# ADCs.net
KiCad netlist of a schematic drawn in Altium Designer
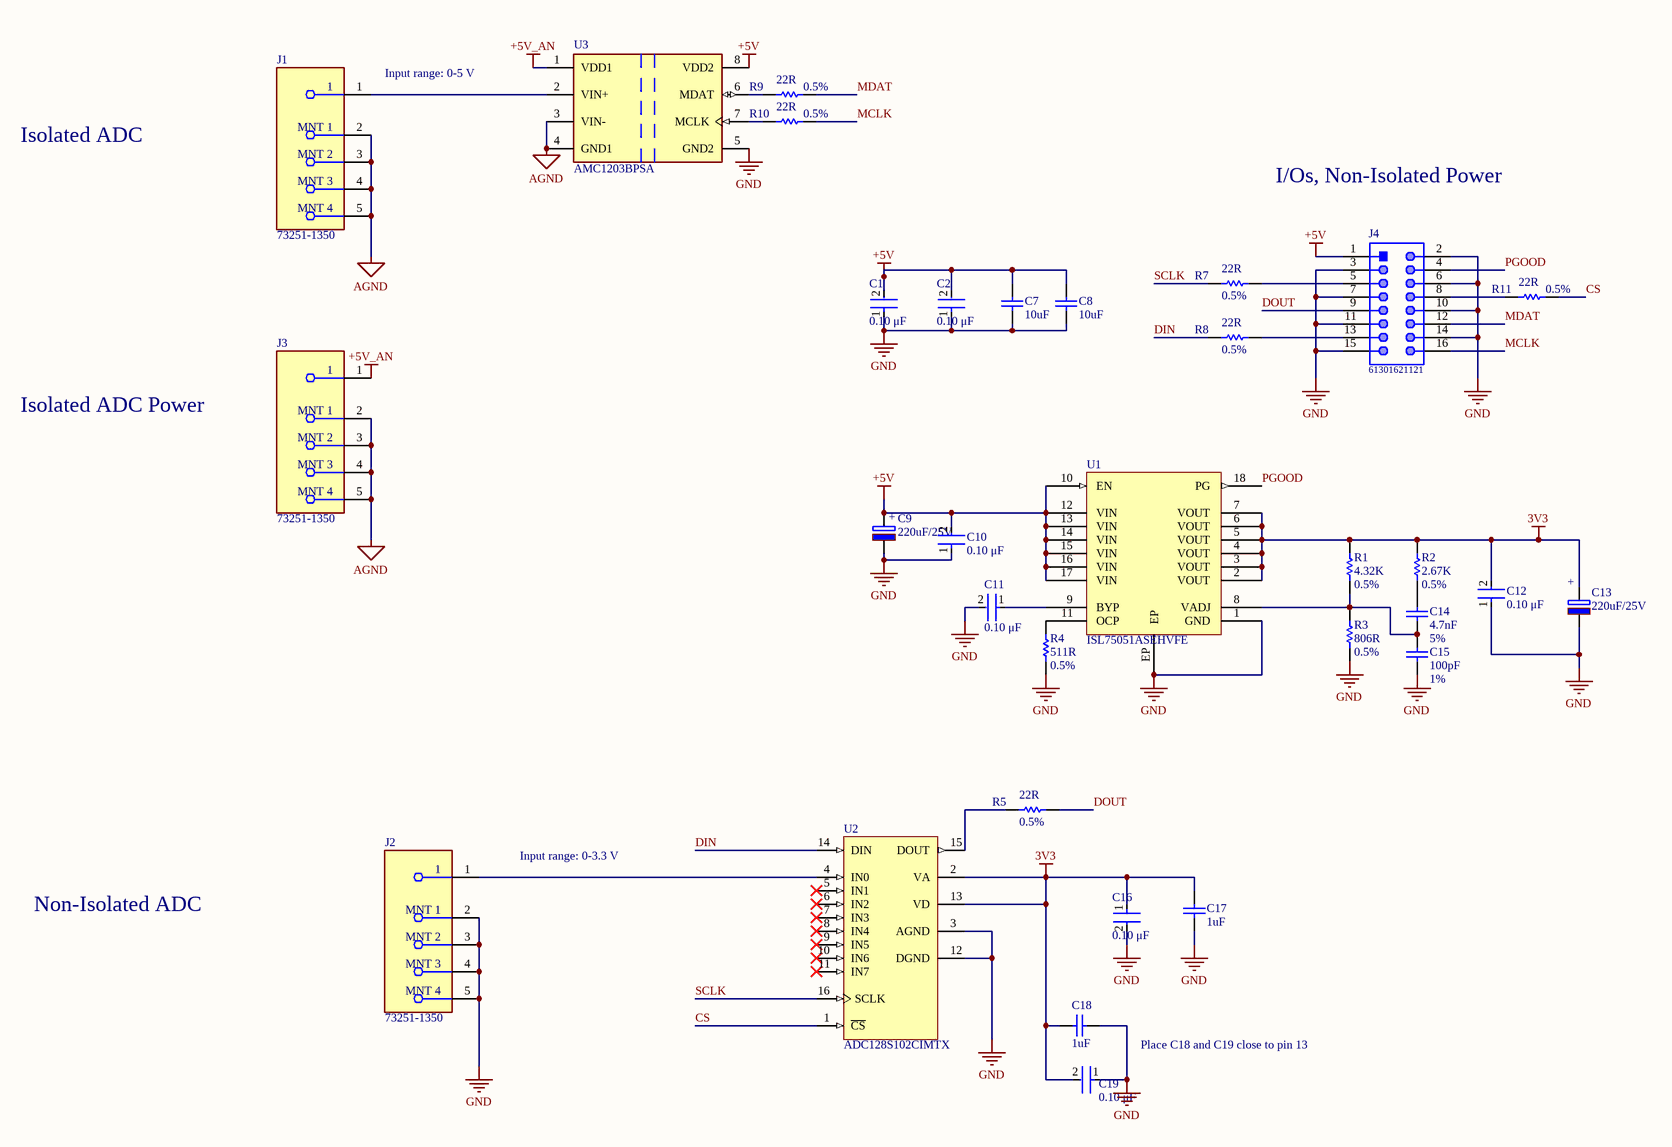
[diagram p0: ADCs.SchDoc]

(export (version "E")
  (design (tool "Eeschema 10.0.6"))
  (components
    (comp (ref "C1")
      (value "0.10 μF")
      (footprint "FP-C0603C-CF-MFG")
      (description "CAP CER 0.1UF 50V 5% X7R 0603")
      (fields (field (name "TOLERANCE") "0.05") (field (name "MANUFACTURER PART NUMBER") "C0603C104J5RACTU"))
      (libsource (lib "Isolated-ADCs") (part "CMP-2006-03056-2"))
    )
    (comp (ref "C2")
      (value "0.10 μF")
      (footprint "FP-C0603C-CF-MFG")
      (description "CAP CER 0.1UF 50V 5% X7R 0603")
      (fields (field (name "TOLERANCE") "0.05") (field (name "MANUFACTURER PART NUMBER") "C0603C104J5RACTU"))
      (libsource (lib "Isolated-ADCs") (part "CMP-2006-03056-2"))
    )
    (comp (ref "C7")
      (value "10uF")
      (footprint "CAPC1608X90N")
      (description "CAP CER 10UF 25V X5R 0603")
      (fields
        (field (name "MANUFACTURER PART NUMBER") "GRM188R61E106KA73D")
        (field (name "MANUFACTURER") "Murata Electronics")
      )
      (libsource (lib "Isolated-ADCs") (part "CAP CER 10UF 25V X5R 0603"))
    )
    (comp (ref "C8")
      (value "10uF")
      (footprint "CAPC1608X90N")
      (description "CAP CER 10UF 25V X5R 0603")
      (fields
        (field (name "MANUFACTURER PART NUMBER") "GRM188R61E106KA73D")
        (field (name "MANUFACTURER") "Murata Electronics")
      )
      (libsource (lib "Isolated-ADCs") (part "CAP CER 10UF 25V X5R 0603"))
    )
    (comp (ref "C9")
      (value "220uF/25V")
      (footprint "CAP_AE830X1050N")
      (description "CAP ALUM 220UF 20% 25V SMD")
      (fields
        (field (name "MANUFACTURER PART NUMBER") "EMZA250ADA221MHA0G")
        (field (name "MANUFACTURER") "United Chemi-Con")
      )
      (libsource (lib "Isolated-ADCs") (part "CAP ALUM 220UF 20% 25V SMD"))
    )
    (comp (ref "C10")
      (value "0.10 μF")
      (footprint "FP-C0603C-CF-MFG")
      (description "CAP CER 0.1UF 50V 5% X7R 0603")
      (fields
        (field (name "MANUFACTURER PART NUMBER") "C0603C104J5RACTU")
        (field (name "MANUFACTURER") "KEMET")
      )
      (libsource (lib "Isolated-ADCs") (part "CMP-2006-03056-2"))
    )
    (comp (ref "C11")
      (value "0.10 μF")
      (footprint "FP-C0603C-CF-MFG")
      (description "CAP CER 0.1UF 50V 5% X7R 0603")
      (fields
        (field (name "MANUFACTURER PART NUMBER") "C0603C104J5RACTU")
        (field (name "MANUFACTURER") "KEMET")
      )
      (libsource (lib "Isolated-ADCs") (part "CMP-2006-03056-2"))
    )
    (comp (ref "C12")
      (value "0.10 μF")
      (footprint "FP-C0603C-CF-MFG")
      (description "CAP CER 0.1UF 50V 5% X7R 0603")
      (fields
        (field (name "MANUFACTURER PART NUMBER") "C0603C104J5RACTU")
        (field (name "MANUFACTURER") "KEMET")
      )
      (libsource (lib "Isolated-ADCs") (part "CMP-2006-03056-2"))
    )
    (comp (ref "C13")
      (value "220uF/25V")
      (footprint "CAP_AE830X1050N")
      (description "CAP ALUM 220UF 20% 25V SMD")
      (fields
        (field (name "MANUFACTURER PART NUMBER") "EMZA250ADA221MHA0G")
        (field (name "MANUFACTURER") "United Chemi-Con")
      )
      (libsource (lib "") (part "CAP ALUM 220UF 20% 25V SMD_1"))
    )
    (comp (ref "C14")
      (value "4.7nF")
      (footprint "CAPC1608X90N")
      (description "CAP CER 4700PF 50V C0G 0603")
      (fields
        (field (name "MANUFACTURER PART NUMBER") "CGA3E2C0G1H472J080AA")
        (field (name "MANUFACTURER") "TDK Corporation")
        (field (name "TOLERANCE") "5%")
      )
      (libsource (lib "Isolated-ADCs") (part "CAP CER 4700PF 50V C0G 0603"))
    )
    (comp (ref "C15")
      (value "100pF")
      (footprint "CAPC1608X90N")
      (description "CAP CER 100PF 50V C0G/NP0 0603")
      (fields
        (field (name "MANUFACTURER PART NUMBER") "06035A101FAT2A")
        (field (name "MANUFACTURER") "KYOCERA AVX")
        (field (name "TOLERANCE") "1%")
      )
      (libsource (lib "Isolated-ADCs") (part "CAP CER 100PF 50V C0G/NP0 0603"))
    )
    (comp (ref "C16")
      (value "0.10 μF")
      (footprint "FP-C0603C-CF-MFG")
      (description "CAP CER 0.1UF 50V 5% X7R 0603")
      (fields (field (name "TOLERANCE") "0.05") (field (name "MANUFACTURER PART NUMBER") "C0603C104J5RACTU"))
      (libsource (lib "Isolated-ADCs") (part "CMP-2006-03056-2"))
    )
    (comp (ref "C17")
      (value "1uF")
      (footprint "CAPC1608X90N")
      (description "CAP CER 1UF 25V X7R 0603")
      (fields
        (field (name "MANUFACTURER PART NUMBER") "GCM188R71E105KA64D")
        (field (name "MANUFACTURER") "Murata Electronics")
      )
      (libsource (lib "Isolated-ADCs") (part "CAP CER 1UF 25V X7R 0603"))
    )
    (comp (ref "C18")
      (value "1uF")
      (footprint "CAPC1608X90N")
      (description "CAP CER 1UF 25V X7R 0603")
      (fields
        (field (name "MANUFACTURER PART NUMBER") "GCM188R71E105KA64D")
        (field (name "MANUFACTURER") "Murata Electronics")
      )
      (libsource (lib "Isolated-ADCs") (part "CAP CER 1UF 25V X7R 0603"))
    )
    (comp (ref "C19")
      (value "0.10 μF")
      (footprint "FP-C0603C-CF-MFG")
      (description "CAP CER 0.1UF 50V 5% X7R 0603")
      (fields (field (name "TOLERANCE") "0.05") (field (name "MANUFACTURER PART NUMBER") "C0603C104J5RACTU"))
      (libsource (lib "Isolated-ADCs") (part "CMP-2006-03056-2"))
    )
    (comp (ref "J1")
      (value "73251-1350")
      (footprint "FP-73251-1350-MFG")
      (description "CONN SMA JACK STR 50 OHM SMD")
      (fields
        (field (name "OCTOPART") "https://octopart.com/73251-1350-molex-5414390")
        (field (name "MANUFACTURER") "Molex")
      )
      (libsource (lib "Isolated-ADCs") (part "CMP-04764-000006-1"))
    )
    (comp (ref "J2")
      (value "73251-1350")
      (footprint "FP-73251-1350-MFG")
      (description "CONN SMA JACK STR 50 OHM SMD")
      (fields
        (field (name "OCTOPART") "https://octopart.com/73251-1350-molex-5414390")
        (field (name "MANUFACTURER") "Molex")
      )
      (libsource (lib "Isolated-ADCs") (part "CMP-04764-000006-1"))
    )
    (comp (ref "J3")
      (value "73251-1350")
      (footprint "FP-73251-1350-MFG")
      (description "CONN SMA JACK STR 50 OHM SMD")
      (fields
        (field (name "OCTOPART") "https://octopart.com/73251-1350-molex-5414390")
        (field (name "MANUFACTURER") "Molex")
      )
      (libsource (lib "Isolated-ADCs") (part "CMP-04764-000006-1"))
    )
    (comp (ref "J4")
      (value "61301621121")
      (footprint "61301621121")
      (description "THT Vertical Pin Header WR-PHD, Pitch 2.54 mm, Dual Row, 16 pins")
      (fields (field (name "MANUFACTURER") "Wurth Elektronik") (field (name "PUBLISHER") "WurthElektronik"))
      (libsource (lib "Isolated-ADCs") (part "CMP-1502-01097-1"))
    )
    (comp (ref "R1")
      (value "4.32K")
      (footprint "RESC1608X55N")
      (description "RES SMD 4.32K OHM 0.5% 1/5W 0603")
      (fields
        (field (name "MANUFACTURER") "Panasonic Electronic Components")
        (field (name "MANUFACTURER PART NUMBER") "ERJ-PB3D4321V")
        (field (name "TOLERANCE") "0.5%")
      )
      (libsource (lib "Isolated-ADCs") (part "RES SMD 4.32K OHM 0.5% 1/5W 0603"))
    )
    (comp (ref "R2")
      (value "2.67K")
      (footprint "RESC1608X55N")
      (description "RES SMD 2.67KOHM 0.5% 1/10W 0603")
      (fields
        (field (name "MANUFACTURER") "Yageo")
        (field (name "MANUFACTURER PART NUMBER") "RT0603DRD072K67L")
        (field (name "TOLERANCE") "0.5%")
      )
      (libsource (lib "Isolated-ADCs") (part "RES SMD 2.67KOHM 0.5% 1/10W 0603"))
    )
    (comp (ref "R3")
      (value "806R")
      (footprint "RESC1608X55N")
      (description "RES SMD 806 OHM 0.5% 1/10W 0603")
      (fields
        (field (name "MANUFACTURER") "Yageo")
        (field (name "MANUFACTURER PART NUMBER") "RT0603DRD0762KL")
        (field (name "TOLERANCE") "0.5%")
      )
      (libsource (lib "Isolated-ADCs") (part "RES SMD 806 OHM 0.5% 1/10W 0603"))
    )
    (comp (ref "R4")
      (value "511R")
      (footprint "RESC1608X55N")
      (description "RES SMD 511 OHM 1% 1/10W 0603")
      (fields
        (field (name "MANUFACTURER") "Panasonic Electronic Components")
        (field (name "MANUFACTURER PART NUMBER") "ERJ-3EKF5110V")
        (field (name "TOLERANCE") "0.5%")
      )
      (libsource (lib "Isolated-ADCs") (part "RES SMD 511 OHM 1% 1/10W 0603"))
    )
    (comp (ref "R5")
      (value "22R")
      (footprint "RESC1608X55N")
      (description "RES SMD 22 OHM 0.5% 1/10W 0603")
      (fields
        (field (name "MANUFACTURER") "Yageo")
        (field (name "MANUFACTURER PART NUMBER") "RT0603DRD0722RL")
        (field (name "TOLERANCE") "0.5%")
      )
      (libsource (lib "Isolated-ADCs") (part "RES SMD 22 OHM 0.5% 1/10W 0603"))
    )
    (comp (ref "R7")
      (value "22R")
      (footprint "RESC1608X55N")
      (description "RES SMD 22 OHM 0.5% 1/10W 0603")
      (fields
        (field (name "MANUFACTURER") "Yageo")
        (field (name "MANUFACTURER PART NUMBER") "RT0603DRD0722RL")
        (field (name "TOLERANCE") "0.5%")
      )
      (libsource (lib "Isolated-ADCs") (part "RES SMD 22 OHM 0.5% 1/10W 0603"))
    )
    (comp (ref "R8")
      (value "22R")
      (footprint "RESC1608X55N")
      (description "RES SMD 22 OHM 0.5% 1/10W 0603")
      (fields
        (field (name "MANUFACTURER") "Yageo")
        (field (name "MANUFACTURER PART NUMBER") "RT0603DRD0722RL")
        (field (name "TOLERANCE") "0.5%")
      )
      (libsource (lib "Isolated-ADCs") (part "RES SMD 22 OHM 0.5% 1/10W 0603"))
    )
    (comp (ref "R9")
      (value "22R")
      (footprint "RESC1608X55N")
      (description "RES SMD 22 OHM 0.5% 1/10W 0603")
      (fields
        (field (name "MANUFACTURER") "Yageo")
        (field (name "MANUFACTURER PART NUMBER") "RT0603DRD0722RL")
        (field (name "TOLERANCE") "0.5%")
      )
      (libsource (lib "Isolated-ADCs") (part "RES SMD 22 OHM 0.5% 1/10W 0603"))
    )
    (comp (ref "R10")
      (value "22R")
      (footprint "RESC1608X55N")
      (description "RES SMD 22 OHM 0.5% 1/10W 0603")
      (fields
        (field (name "MANUFACTURER") "Yageo")
        (field (name "MANUFACTURER PART NUMBER") "RT0603DRD0722RL")
        (field (name "TOLERANCE") "0.5%")
      )
      (libsource (lib "Isolated-ADCs") (part "RES SMD 22 OHM 0.5% 1/10W 0603"))
    )
    (comp (ref "R11")
      (value "22R")
      (footprint "RESC1608X55N")
      (description "RES SMD 22 OHM 0.5% 1/10W 0603")
      (fields
        (field (name "MANUFACTURER") "Yageo")
        (field (name "MANUFACTURER PART NUMBER") "RT0603DRD0722RL")
        (field (name "TOLERANCE") "0.5%")
      )
      (libsource (lib "Isolated-ADCs") (part "RES SMD 22 OHM 0.5% 1/10W 0603"))
    )
    (comp (ref "U1")
      (value "ISL75051ASEHVFE")
      (footprint "CFP102P1520X310-18AN")
      (description "Voltage regulator, linear, variable, 3 A, CFP-18 exposed pad, class V")
      (fields
        (field (name "MANUFACTURER") "Renesas / Intersil")
        (field (name "FM (SMD) PART NUMBER") "5962R1121203VYC")
      )
      (libsource (lib "Isolated-ADCs") (part "ISL75051ASEHVFE"))
    )
    (comp (ref "U2")
      (value "ADC128S102CIMTX")
      (footprint "MTC16_N")
      (description "8-Channel, 500 kSPS to 1 MSPS, 12-Bit A/D Converter, 16-pin TSSOP")
      (fields (field (name "MANUFACTURER") "National Semiconductor"))
      (libsource (lib "Isolated-ADCs") (part "CMP-0054-00337-2"))
    )
    (comp (ref "U3")
      (value "AMC1203BPSA")
      (footprint "FP-PSA0008A-IPC_C")
      (description "IC ADC 16BIT SIGMA-DELTA 8SOP")
      (libsource (lib "Isolated-ADCs") (part "CMP-04860-000036-1"))
    )
  )
  (nets
    (net (code "1") (name "+5V") (class "Default")
      (node (ref "C1") (pin "2") (pinfunction "2_2") (pintype "passive"))
      (node (ref "C10") (pin "2") (pinfunction "2_2") (pintype "passive"))
      (node (ref "C2") (pin "2") (pinfunction "2_2") (pintype "passive"))
      (node (ref "C7") (pin "1") (pinfunction "1_1") (pintype "passive"))
      (node (ref "C8") (pin "1") (pinfunction "1_1") (pintype "passive"))
      (node (ref "C9") (pin "1") (pinfunction "1_1") (pintype "passive"))
      (node (ref "J4") (pin "1") (pinfunction "1_1") (pintype "passive"))
      (node (ref "U1") (pin "10") (pinfunction "EN_10") (pintype "input"))
      (node (ref "U1") (pin "12") (pinfunction "VIN_12") (pintype "power_in"))
      (node (ref "U1") (pin "13") (pinfunction "VIN_13") (pintype "power_in"))
      (node (ref "U1") (pin "14") (pinfunction "VIN_14") (pintype "power_in"))
      (node (ref "U1") (pin "15") (pinfunction "VIN_15") (pintype "power_in"))
      (node (ref "U1") (pin "16") (pinfunction "VIN_16") (pintype "power_in"))
      (node (ref "U1") (pin "17") (pinfunction "VIN_17") (pintype "power_in"))
      (node (ref "U3") (pin "8") (pinfunction "VDD2_8") (pintype "power_in"))
    )
    (net (code "2") (name "+5V_AN") (class "Default")
      (node (ref "J3") (pin "1") (pinfunction "1_1") (pintype "passive"))
      (node (ref "U3") (pin "1") (pinfunction "VDD1_1") (pintype "power_in"))
    )
    (net (code "3") (name "/CS") (class "Default")
      (node (ref "R11") (pin "2") (pinfunction "2_2") (pintype "passive"))
      (node (ref "U2") (pin "1") (pinfunction "~{CS}_1") (pintype "input"))
    )
    (net (code "4") (name "/DIN") (class "Default")
      (node (ref "R8") (pin "1") (pinfunction "1_1") (pintype "passive"))
      (node (ref "U2") (pin "14") (pinfunction "DIN_14") (pintype "input"))
    )
    (net (code "5") (name "/DOUT") (class "Default")
      (node (ref "J4") (pin "9") (pinfunction "9_9") (pintype "passive"))
      (node (ref "R5") (pin "2") (pinfunction "2_2") (pintype "passive"))
    )
    (net (code "6") (name "/MCLK") (class "Default")
      (node (ref "J4") (pin "16") (pinfunction "16_16") (pintype "passive"))
      (node (ref "R10") (pin "2") (pinfunction "2_2") (pintype "passive"))
    )
    (net (code "7") (name "/MDAT") (class "Default")
      (node (ref "J4") (pin "12") (pinfunction "12_12") (pintype "passive"))
      (node (ref "R9") (pin "2") (pinfunction "2_2") (pintype "passive"))
    )
    (net (code "8") (name "/PGOOD") (class "Default")
      (node (ref "J4") (pin "4") (pinfunction "4_4") (pintype "passive"))
      (node (ref "U1") (pin "18") (pinfunction "PG_18") (pintype "output"))
    )
    (net (code "9") (name "/SCLK") (class "Default")
      (node (ref "R7") (pin "1") (pinfunction "1_1") (pintype "passive"))
      (node (ref "U2") (pin "16") (pinfunction "SCLK_16") (pintype "input"))
    )
    (net (code "10") (name "3V3") (class "Default")
      (node (ref "C12") (pin "2") (pinfunction "2_2") (pintype "passive"))
      (node (ref "C13") (pin "1") (pinfunction "1_1") (pintype "passive"))
      (node (ref "C16") (pin "1") (pinfunction "1_1") (pintype "passive"))
      (node (ref "C17") (pin "1") (pinfunction "1_1") (pintype "passive"))
      (node (ref "C18") (pin "2") (pinfunction "2_2") (pintype "passive"))
      (node (ref "C19") (pin "2") (pinfunction "2_2") (pintype "passive"))
      (node (ref "R1") (pin "2") (pinfunction "2_2") (pintype "passive"))
      (node (ref "R2") (pin "2") (pinfunction "2_2") (pintype "passive"))
      (node (ref "U1") (pin "2") (pinfunction "VOUT_2") (pintype "power_in"))
      (node (ref "U1") (pin "3") (pinfunction "VOUT_3") (pintype "power_in"))
      (node (ref "U1") (pin "4") (pinfunction "VOUT_4") (pintype "power_in"))
      (node (ref "U1") (pin "5") (pinfunction "VOUT_5") (pintype "power_in"))
      (node (ref "U1") (pin "6") (pinfunction "VOUT_6") (pintype "power_in"))
      (node (ref "U1") (pin "7") (pinfunction "VOUT_7") (pintype "power_in"))
      (node (ref "U2") (pin "13") (pinfunction "VD_13") (pintype "power_in"))
      (node (ref "U2") (pin "2") (pinfunction "VA_2") (pintype "power_in"))
    )
    (net (code "11") (name "AGND") (class "Default")
      (node (ref "J1") (pin "2") (pinfunction "MNT_1_2") (pintype "passive"))
      (node (ref "J1") (pin "3") (pinfunction "MNT_2_3") (pintype "passive"))
      (node (ref "J1") (pin "4") (pinfunction "MNT_3_4") (pintype "passive"))
      (node (ref "J1") (pin "5") (pinfunction "MNT_4_5") (pintype "passive"))
      (node (ref "J3") (pin "2") (pinfunction "MNT_1_2") (pintype "passive"))
      (node (ref "J3") (pin "3") (pinfunction "MNT_2_3") (pintype "passive"))
      (node (ref "J3") (pin "4") (pinfunction "MNT_3_4") (pintype "passive"))
      (node (ref "J3") (pin "5") (pinfunction "MNT_4_5") (pintype "passive"))
      (node (ref "U3") (pin "3") (pinfunction "VIN-_3") (pintype "tri_state"))
      (node (ref "U3") (pin "4") (pinfunction "GND1_4") (pintype "power_in"))
    )
    (net (code "12") (name "GND") (class "Default")
      (node (ref "C1") (pin "1") (pinfunction "1_1") (pintype "passive"))
      (node (ref "C10") (pin "1") (pinfunction "1_1") (pintype "passive"))
      (node (ref "C11") (pin "2") (pinfunction "2_2") (pintype "passive"))
      (node (ref "C12") (pin "1") (pinfunction "1_1") (pintype "passive"))
      (node (ref "C13") (pin "2") (pinfunction "2_2") (pintype "passive"))
      (node (ref "C15") (pin "2") (pinfunction "2_2") (pintype "passive"))
      (node (ref "C16") (pin "2") (pinfunction "2_2") (pintype "passive"))
      (node (ref "C17") (pin "2") (pinfunction "2_2") (pintype "passive"))
      (node (ref "C18") (pin "1") (pinfunction "1_1") (pintype "passive"))
      (node (ref "C19") (pin "1") (pinfunction "1_1") (pintype "passive"))
      (node (ref "C2") (pin "1") (pinfunction "1_1") (pintype "passive"))
      (node (ref "C7") (pin "2") (pinfunction "2_2") (pintype "passive"))
      (node (ref "C8") (pin "2") (pinfunction "2_2") (pintype "passive"))
      (node (ref "C9") (pin "2") (pinfunction "2_2") (pintype "passive"))
      (node (ref "J2") (pin "2") (pinfunction "MNT_1_2") (pintype "passive"))
      (node (ref "J2") (pin "3") (pinfunction "MNT_2_3") (pintype "passive"))
      (node (ref "J2") (pin "4") (pinfunction "MNT_3_4") (pintype "passive"))
      (node (ref "J2") (pin "5") (pinfunction "MNT_4_5") (pintype "passive"))
      (node (ref "J4") (pin "10") (pinfunction "10_10") (pintype "passive"))
      (node (ref "J4") (pin "11") (pinfunction "11_11") (pintype "passive"))
      (node (ref "J4") (pin "14") (pinfunction "14_14") (pintype "passive"))
      (node (ref "J4") (pin "15") (pinfunction "15_15") (pintype "passive"))
      (node (ref "J4") (pin "2") (pinfunction "2_2") (pintype "passive"))
      (node (ref "J4") (pin "3") (pinfunction "3_3") (pintype "passive"))
      (node (ref "J4") (pin "6") (pinfunction "6_6") (pintype "passive"))
      (node (ref "J4") (pin "7") (pinfunction "7_7") (pintype "passive"))
      (node (ref "R3") (pin "1") (pinfunction "1_1") (pintype "passive"))
      (node (ref "R4") (pin "1") (pinfunction "1_1") (pintype "passive"))
      (node (ref "U1") (pin "1") (pinfunction "GND_1") (pintype "power_in"))
      (node (ref "U1") (pin "EP") (pinfunction "EP_EP") (pintype "passive"))
      (node (ref "U2") (pin "12") (pinfunction "DGND_12") (pintype "power_in"))
      (node (ref "U2") (pin "3") (pinfunction "AGND_3") (pintype "power_in"))
      (node (ref "U3") (pin "5") (pinfunction "GND2_5") (pintype "power_in"))
    )
    (net (code "13") (name "Net-(C14-Pad1)") (class "Default")
      (node (ref "C14") (pin "1") (pinfunction "1_1") (pintype "passive"))
      (node (ref "R2") (pin "1") (pinfunction "1_1") (pintype "passive"))
    )
    (net (code "14") (name "Net-(J4-Pad5)") (class "Default")
      (node (ref "J4") (pin "5") (pinfunction "5_5") (pintype "passive"))
      (node (ref "R7") (pin "2") (pinfunction "2_2") (pintype "passive"))
    )
    (net (code "15") (name "Net-(J4-Pad8)") (class "Default")
      (node (ref "J4") (pin "8") (pinfunction "8_8") (pintype "passive"))
      (node (ref "R11") (pin "1") (pinfunction "1_1") (pintype "passive"))
    )
    (net (code "16") (name "Net-(J4-Pad13)") (class "Default")
      (node (ref "J4") (pin "13") (pinfunction "13_13") (pintype "passive"))
      (node (ref "R8") (pin "2") (pinfunction "2_2") (pintype "passive"))
    )
    (net (code "17") (name "Net-(U1-BYP)") (class "Default")
      (node (ref "C11") (pin "1") (pinfunction "1_1") (pintype "passive"))
      (node (ref "U1") (pin "9") (pinfunction "BYP_9") (pintype "passive"))
    )
    (net (code "18") (name "Net-(U1-OCP)") (class "Default")
      (node (ref "R4") (pin "2") (pinfunction "2_2") (pintype "passive"))
      (node (ref "U1") (pin "11") (pinfunction "OCP_11") (pintype "passive"))
    )
    (net (code "19") (name "Net-(U1-VADJ)") (class "Default")
      (node (ref "C14") (pin "2") (pinfunction "2_2") (pintype "passive"))
      (node (ref "C15") (pin "1") (pinfunction "1_1") (pintype "passive"))
      (node (ref "R1") (pin "1") (pinfunction "1_1") (pintype "passive"))
      (node (ref "R3") (pin "2") (pinfunction "2_2") (pintype "passive"))
      (node (ref "U1") (pin "8") (pinfunction "VADJ_8") (pintype "passive"))
    )
    (net (code "20") (name "Net-(U2-DOUT)") (class "Default")
      (node (ref "R5") (pin "1") (pinfunction "1_1") (pintype "passive"))
      (node (ref "U2") (pin "15") (pinfunction "DOUT_15") (pintype "output"))
    )
    (net (code "21") (name "Net-(U2-IN0)") (class "Default")
      (node (ref "J2") (pin "1") (pinfunction "1_1") (pintype "passive"))
      (node (ref "U2") (pin "4") (pinfunction "IN0_4") (pintype "input"))
    )
    (net (code "22") (name "Net-(U3-MCLK)") (class "Default")
      (node (ref "R10") (pin "1") (pinfunction "1_1") (pintype "passive"))
      (node (ref "U3") (pin "7") (pinfunction "MCLK_7") (pintype "input"))
    )
    (net (code "23") (name "Net-(U3-MDAT)") (class "Default")
      (node (ref "R9") (pin "1") (pinfunction "1_1") (pintype "passive"))
      (node (ref "U3") (pin "6") (pinfunction "MDAT_6") (pintype "bidirectional"))
    )
    (net (code "24") (name "Net-(U3-VIN+)") (class "Default")
      (node (ref "J1") (pin "1") (pinfunction "1_1") (pintype "passive"))
      (node (ref "U3") (pin "2") (pinfunction "VIN+_2") (pintype "tri_state"))
    )
    (net (code "25") (name "unconnected-(U2-IN1-Pad5)") (class "Default")
      (node (ref "U2") (pin "5") (pinfunction "IN1_5") (pintype "input+no_connect"))
    )
    (net (code "26") (name "unconnected-(U2-IN2-Pad6)") (class "Default")
      (node (ref "U2") (pin "6") (pinfunction "IN2_6") (pintype "input+no_connect"))
    )
    (net (code "27") (name "unconnected-(U2-IN3-Pad7)") (class "Default")
      (node (ref "U2") (pin "7") (pinfunction "IN3_7") (pintype "input+no_connect"))
    )
    (net (code "28") (name "unconnected-(U2-IN4-Pad8)") (class "Default")
      (node (ref "U2") (pin "8") (pinfunction "IN4_8") (pintype "input+no_connect"))
    )
    (net (code "29") (name "unconnected-(U2-IN5-Pad9)") (class "Default")
      (node (ref "U2") (pin "9") (pinfunction "IN5_9") (pintype "input+no_connect"))
    )
    (net (code "30") (name "unconnected-(U2-IN6-Pad10)") (class "Default")
      (node (ref "U2") (pin "10") (pinfunction "IN6_10") (pintype "input+no_connect"))
    )
    (net (code "31") (name "unconnected-(U2-IN7-Pad11)") (class "Default")
      (node (ref "U2") (pin "11") (pinfunction "IN7_11") (pintype "input+no_connect"))
    )
  )
)
